# Mareltek_Glove_Project_esp32.net
KiCad netlist of a schematic drawn in EAGLE
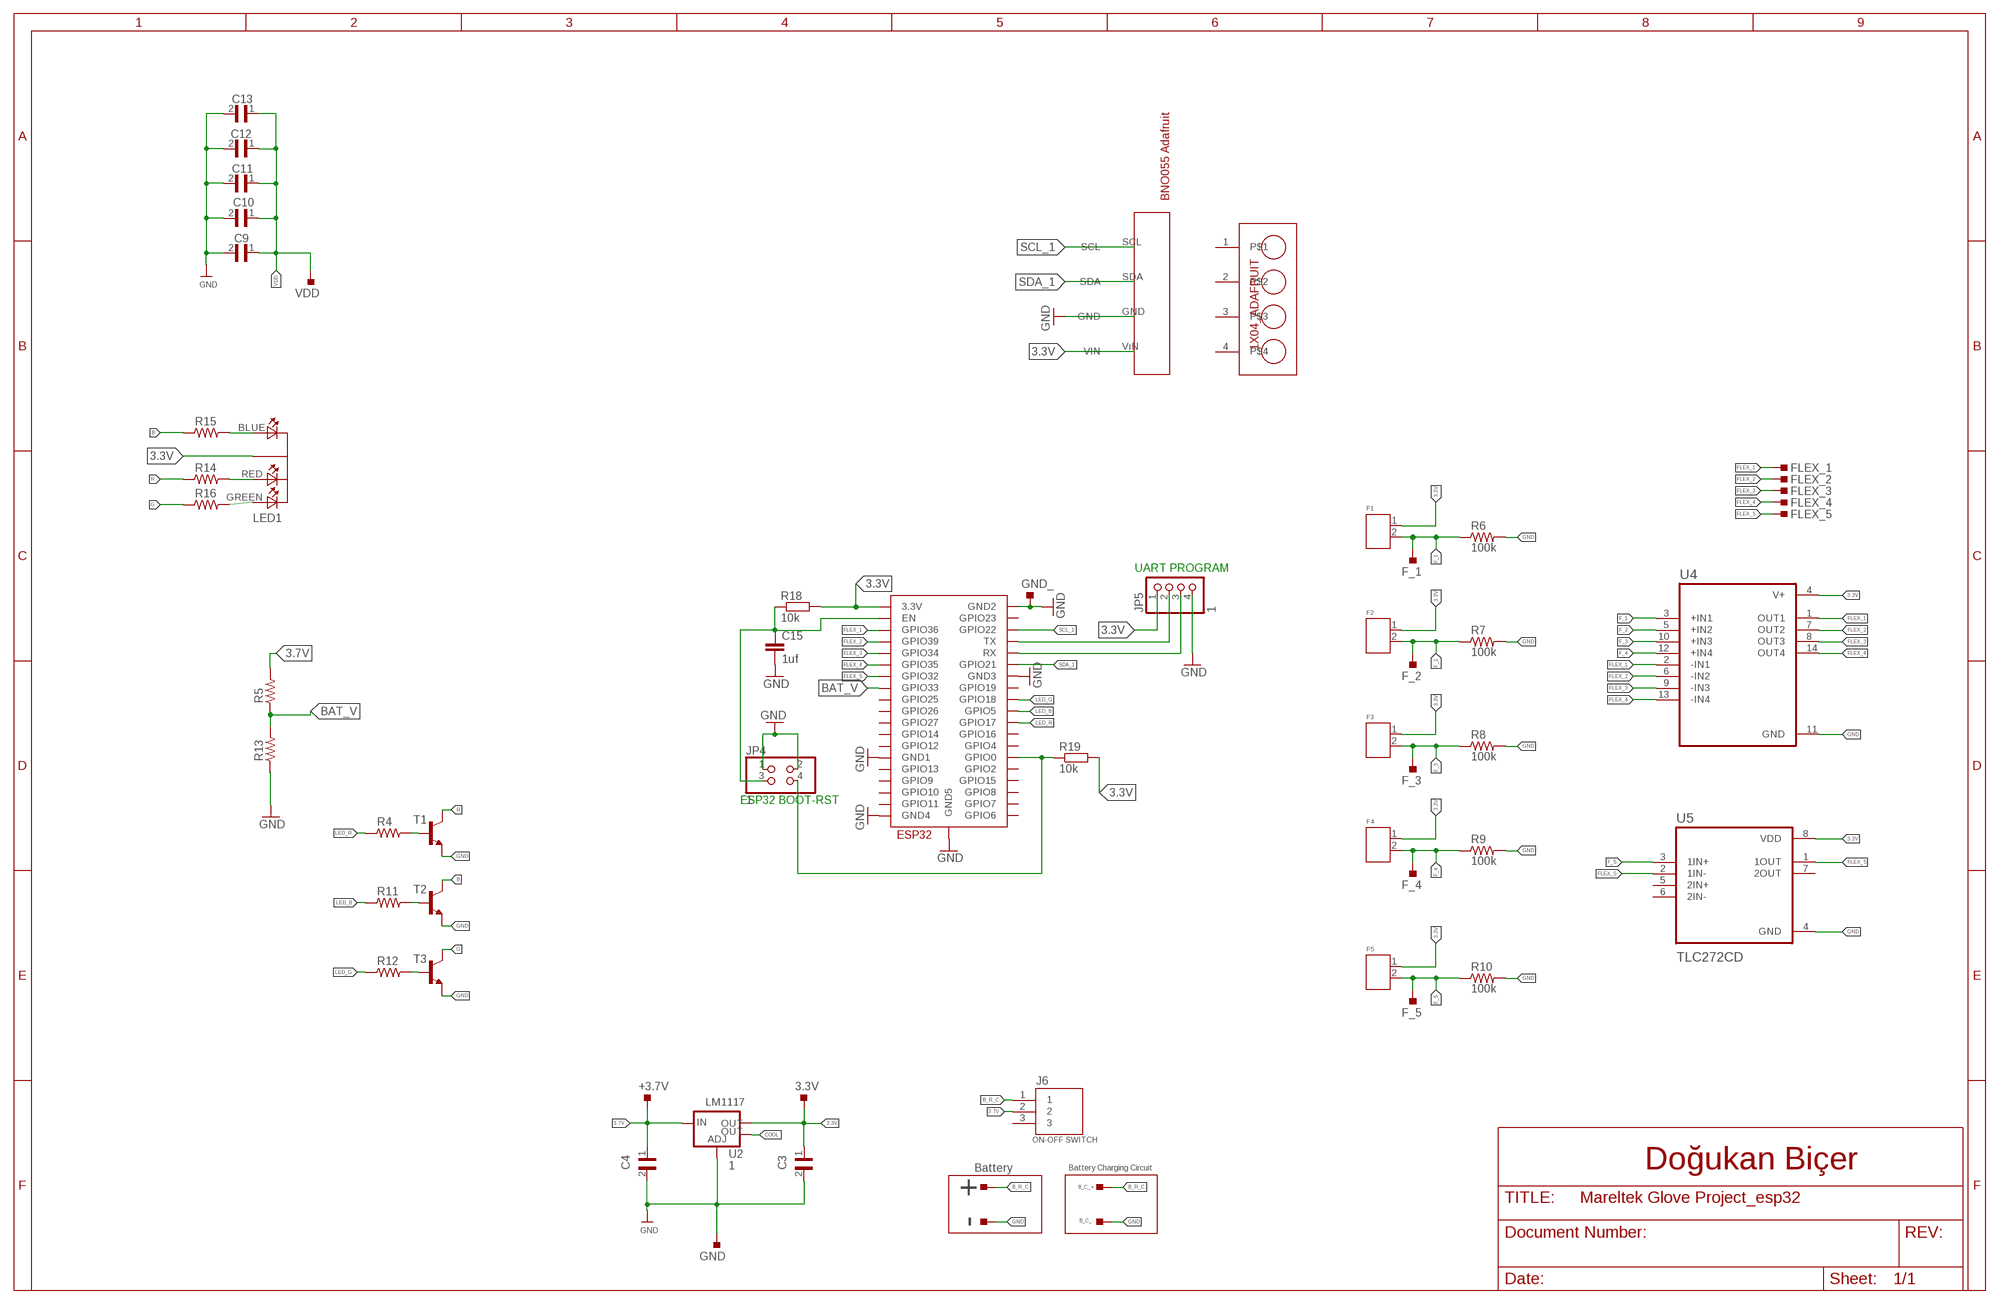
[diagram p0: schematic, sheet 1]

(export (version "E")
  (design (tool "Eeschema 10.0.6"))
  (components
    (comp (ref "+")
      (value "TESTPOINT_TPS-PAD-036")
      (footprint "eagle-import:TESTPOINT_PAD-036")
      (libsource (lib "eagle-import") (part "TESTPOINT_TPS-PAD-036"))
    )
    (comp (ref "+3.7V")
      (value "TESTPOINT_TPS-SMD-10SN")
      (footprint "eagle-import:TESTPOINT_SMD-10SN")
      (libsource (lib "eagle-import") (part "Mareltek Detector Hand Library_TESTPOINT_TPS-SMD-10SN"))
    )
    (comp (ref "-")
      (value "TESTPOINT_TPS-PAD-036")
      (footprint "eagle-import:TESTPOINT_PAD-036")
      (libsource (lib "eagle-import") (part "TESTPOINT_TPS-PAD-036"))
    )
    (comp (ref "3.3V")
      (value "TESTPOINT_TPS-SMD-10SN")
      (footprint "eagle-import:TESTPOINT_SMD-10SN")
      (libsource (lib "eagle-import") (part "Mareltek Detector Hand Library_TESTPOINT_TPS-SMD-10SN"))
    )
    (comp (ref "B_C_+")
      (value "TESTPOINT_TPS-PAD-036")
      (footprint "eagle-import:TESTPOINT_PAD-036")
      (libsource (lib "eagle-import") (part "TESTPOINT_TPS-PAD-036"))
    )
    (comp (ref "B_C_-")
      (value "TESTPOINT_TPS-PAD-036")
      (footprint "eagle-import:TESTPOINT_PAD-036")
      (libsource (lib "eagle-import") (part "TESTPOINT_TPS-PAD-036"))
    )
    (comp (ref "C3")
      (value "10uF")
      (footprint "eagle-import:CAPC1608X90")
      (fields (field (name "MF") "AVX") (field (name "MP") "06033C391KAT4A") (field (name "SPICEPREFIX") "C"))
      (libsource (lib "eagle-import") (part "CAP_0603"))
    )
    (comp (ref "C4")
      (value "10uF")
      (footprint "eagle-import:CAPC1608X90")
      (fields (field (name "MF") "AVX") (field (name "MP") "06033C391KAT4A") (field (name "SPICEPREFIX") "C"))
      (libsource (lib "eagle-import") (part "CAP_0603"))
    )
    (comp (ref "C9")
      (value "100nF")
      (footprint "eagle-import:CAPC1608X90")
      (fields (field (name "MF") "AVX") (field (name "MP") "06033C391KAT4A") (field (name "SPICEPREFIX") "C"))
      (libsource (lib "eagle-import") (part "CAP_0603"))
    )
    (comp (ref "C10")
      (value "100nF")
      (footprint "eagle-import:CAPC1608X90")
      (fields (field (name "MF") "AVX") (field (name "MP") "06033C391KAT4A") (field (name "SPICEPREFIX") "C"))
      (libsource (lib "eagle-import") (part "CAP_0603"))
    )
    (comp (ref "C11")
      (value "100nF")
      (footprint "eagle-import:CAPC1608X90")
      (fields (field (name "MF") "AVX") (field (name "MP") "06033C391KAT4A") (field (name "SPICEPREFIX") "C"))
      (libsource (lib "eagle-import") (part "CAP_0603"))
    )
    (comp (ref "C12")
      (value "100nF")
      (footprint "eagle-import:CAPC1608X90")
      (fields (field (name "MF") "AVX") (field (name "MP") "06033C391KAT4A") (field (name "SPICEPREFIX") "C"))
      (libsource (lib "eagle-import") (part "CAP_0603"))
    )
    (comp (ref "C13")
      (value "100nF")
      (footprint "eagle-import:CAPC1608X90")
      (fields (field (name "MF") "AVX") (field (name "MP") "06033C391KAT4A") (field (name "SPICEPREFIX") "C"))
      (libsource (lib "eagle-import") (part "CAP_0603"))
    )
    (comp (ref "C15")
      (value "1uf")
      (footprint "eagle-import:C0805")
      (libsource (lib "eagle-import") (part "C-EUC0805"))
    )
    (comp (ref "F1")
      (value "FLEX_CONNECTOR")
      (footprint "eagle-import:FLEX_CONNECTOR")
      (libsource (lib "eagle-import") (part "FLEX_CONNECTOR"))
    )
    (comp (ref "F2")
      (value "FLEX_CONNECTOR")
      (footprint "eagle-import:FLEX_CONNECTOR")
      (libsource (lib "eagle-import") (part "FLEX_CONNECTOR"))
    )
    (comp (ref "F3")
      (value "FLEX_CONNECTOR")
      (footprint "eagle-import:FLEX_CONNECTOR")
      (libsource (lib "eagle-import") (part "FLEX_CONNECTOR"))
    )
    (comp (ref "F4")
      (value "FLEX_CONNECTOR")
      (footprint "eagle-import:FLEX_CONNECTOR")
      (libsource (lib "eagle-import") (part "FLEX_CONNECTOR"))
    )
    (comp (ref "F5")
      (value "FLEX_CONNECTOR")
      (footprint "eagle-import:FLEX_CONNECTOR")
      (libsource (lib "eagle-import") (part "FLEX_CONNECTOR"))
    )
    (comp (ref "FLEX_1")
      (value "TESTPOINT_TPS-SMD-10SN")
      (footprint "eagle-import:TESTPOINT_SMD-10SN")
      (libsource (lib "eagle-import") (part "Mareltek Detector Hand Library_TESTPOINT_TPS-SMD-10SN"))
    )
    (comp (ref "FLEX_2")
      (value "TESTPOINT_TPS-SMD-10SN")
      (footprint "eagle-import:TESTPOINT_SMD-10SN")
      (libsource (lib "eagle-import") (part "Mareltek Detector Hand Library_TESTPOINT_TPS-SMD-10SN"))
    )
    (comp (ref "FLEX_3")
      (value "TESTPOINT_TPS-SMD-10SN")
      (footprint "eagle-import:TESTPOINT_SMD-10SN")
      (libsource (lib "eagle-import") (part "Mareltek Detector Hand Library_TESTPOINT_TPS-SMD-10SN"))
    )
    (comp (ref "FLEX_4")
      (value "TESTPOINT_TPS-SMD-10SN")
      (footprint "eagle-import:TESTPOINT_SMD-10SN")
      (libsource (lib "eagle-import") (part "Mareltek Detector Hand Library_TESTPOINT_TPS-SMD-10SN"))
    )
    (comp (ref "FLEX_5")
      (value "TESTPOINT_TPS-SMD-10SN")
      (footprint "eagle-import:TESTPOINT_SMD-10SN")
      (libsource (lib "eagle-import") (part "Mareltek Detector Hand Library_TESTPOINT_TPS-SMD-10SN"))
    )
    (comp (ref "F_1")
      (value "TESTPOINT_TPS-SMD-10SN")
      (footprint "eagle-import:TESTPOINT_SMD-10SN")
      (libsource (lib "eagle-import") (part "Mareltek Detector Hand Library_TESTPOINT_TPS-SMD-10SN"))
    )
    (comp (ref "F_2")
      (value "TESTPOINT_TPS-SMD-10SN")
      (footprint "eagle-import:TESTPOINT_SMD-10SN")
      (libsource (lib "eagle-import") (part "Mareltek Detector Hand Library_TESTPOINT_TPS-SMD-10SN"))
    )
    (comp (ref "F_3")
      (value "TESTPOINT_TPS-SMD-10SN")
      (footprint "eagle-import:TESTPOINT_SMD-10SN")
      (libsource (lib "eagle-import") (part "Mareltek Detector Hand Library_TESTPOINT_TPS-SMD-10SN"))
    )
    (comp (ref "F_4")
      (value "TESTPOINT_TPS-SMD-10SN")
      (footprint "eagle-import:TESTPOINT_SMD-10SN")
      (libsource (lib "eagle-import") (part "Mareltek Detector Hand Library_TESTPOINT_TPS-SMD-10SN"))
    )
    (comp (ref "F_5")
      (value "TESTPOINT_TPS-SMD-10SN")
      (footprint "eagle-import:TESTPOINT_SMD-10SN")
      (libsource (lib "eagle-import") (part "Mareltek Detector Hand Library_TESTPOINT_TPS-SMD-10SN"))
    )
    (comp (ref "GND")
      (value "TESTPOINT_TPS-SMD-10SN")
      (footprint "eagle-import:TESTPOINT_SMD-10SN")
      (libsource (lib "eagle-import") (part "Mareltek Detector Hand Library_TESTPOINT_TPS-SMD-10SN"))
    )
    (comp (ref "GND_")
      (value "TESTPOINT_TPS-SMD-10SN")
      (footprint "eagle-import:TESTPOINT_SMD-10SN")
      (libsource (lib "eagle-import") (part "Mareltek Detector Hand Library_TESTPOINT_TPS-SMD-10SN"))
    )
    (comp (ref "J6")
      (value "ON-OFF SWITCH")
      (footprint "eagle-import:TE_5-146293-3")
      (fields
        (field (name "COMMENT") "5-146293-3")
        (field (name "MF") "TE Connectivity")
        (field (name "SPICEPREFIX") "J")
      )
      (libsource (lib "eagle-import") (part "BUTTONS"))
    )
    (comp (ref "JP4")
      (value "1")
      (footprint "eagle-import:2X02")
      (libsource (lib "eagle-import") (part "PINHD-2X2"))
    )
    (comp (ref "JP5")
      (value "1")
      (footprint "eagle-import:1X04")
      (libsource (lib "eagle-import") (part "PINHD-1X4"))
    )
    (comp (ref "LED1")
      (value "LED-DIP-3")
      (footprint "eagle-import:DIP-4")
      (libsource (lib "eagle-import") (part "LED-DIP-3"))
    )
    (comp (ref "R4")
      (value "100R")
      (footprint "eagle-import:RC-MASTER-SMD_R0603MP")
      (fields (field (name "SPICEPREFIX") "R"))
      (libsource (lib "eagle-import") (part "RC-MASTER-SMD_RESISTOR0603MP"))
    )
    (comp (ref "R5")
      (value "100k")
      (footprint "eagle-import:RC-MASTER-SMD_R0603MP")
      (fields (field (name "SPICEPREFIX") "R"))
      (libsource (lib "eagle-import") (part "RC-MASTER-SMD_RESISTOR0603MP"))
    )
    (comp (ref "R6")
      (value "100k")
      (footprint "eagle-import:RC-MASTER-SMD_R0603MP")
      (fields (field (name "SPICEPREFIX") "W"))
      (libsource (lib "eagle-import") (part "RC-MASTER-SMD_RESISTOR0603MP"))
    )
    (comp (ref "R7")
      (value "100k")
      (footprint "eagle-import:RC-MASTER-SMD_R0603MP")
      (fields (field (name "SPICEPREFIX") "W"))
      (libsource (lib "eagle-import") (part "RC-MASTER-SMD_RESISTOR0603MP"))
    )
    (comp (ref "R8")
      (value "100k")
      (footprint "eagle-import:RC-MASTER-SMD_R0603MP")
      (fields (field (name "SPICEPREFIX") "W"))
      (libsource (lib "eagle-import") (part "RC-MASTER-SMD_RESISTOR0603MP"))
    )
    (comp (ref "R9")
      (value "100k")
      (footprint "eagle-import:RC-MASTER-SMD_R0603MP")
      (fields (field (name "SPICEPREFIX") "W"))
      (libsource (lib "eagle-import") (part "RC-MASTER-SMD_RESISTOR0603MP"))
    )
    (comp (ref "R10")
      (value "100k")
      (footprint "eagle-import:RC-MASTER-SMD_R0603MP")
      (fields (field (name "SPICEPREFIX") "W"))
      (libsource (lib "eagle-import") (part "RC-MASTER-SMD_RESISTOR0603MP"))
    )
    (comp (ref "R11")
      (value "100R")
      (footprint "eagle-import:RC-MASTER-SMD_R0603MP")
      (fields (field (name "SPICEPREFIX") "R"))
      (libsource (lib "eagle-import") (part "RC-MASTER-SMD_RESISTOR0603MP"))
    )
    (comp (ref "R12")
      (value "100R")
      (footprint "eagle-import:RC-MASTER-SMD_R0603MP")
      (fields (field (name "SPICEPREFIX") "R"))
      (libsource (lib "eagle-import") (part "RC-MASTER-SMD_RESISTOR0603MP"))
    )
    (comp (ref "R13")
      (value "330R")
      (footprint "eagle-import:RC-MASTER-SMD_R0603MP")
      (fields (field (name "SPICEPREFIX") "R"))
      (libsource (lib "eagle-import") (part "RC-MASTER-SMD_RESISTOR0603MP"))
    )
    (comp (ref "R14")
      (value "100R")
      (footprint "eagle-import:RC-MASTER-SMD_R0603MP")
      (fields (field (name "SPICEPREFIX") "R"))
      (libsource (lib "eagle-import") (part "RC-MASTER-SMD_RESISTOR0603MP"))
    )
    (comp (ref "R15")
      (value "100R")
      (footprint "eagle-import:RC-MASTER-SMD_R0603MP")
      (fields (field (name "SPICEPREFIX") "R"))
      (libsource (lib "eagle-import") (part "RC-MASTER-SMD_RESISTOR0603MP"))
    )
    (comp (ref "R16")
      (value "100R")
      (footprint "eagle-import:RC-MASTER-SMD_R0603MP")
      (fields (field (name "SPICEPREFIX") "R"))
      (libsource (lib "eagle-import") (part "RC-MASTER-SMD_RESISTOR0603MP"))
    )
    (comp (ref "R18")
      (value "10k")
      (footprint "eagle-import:R0603")
      (libsource (lib "eagle-import") (part "R-EU_R0603"))
    )
    (comp (ref "R19")
      (value "10k")
      (footprint "eagle-import:R0603")
      (libsource (lib "eagle-import") (part "R-EU_R0603"))
    )
    (comp (ref "T1")
      (value "TRANSISTORBC846BLT1SOT23-BEC")
      (footprint "eagle-import:SOT23-BEC")
      (libsource (lib "eagle-import") (part "TRANSISTORSOT23-BECBC846BLT1"))
    )
    (comp (ref "T2")
      (value "TRANSISTORBC846BLT1SOT23-BEC")
      (footprint "eagle-import:SOT23-BEC")
      (libsource (lib "eagle-import") (part "TRANSISTORSOT23-BECBC846BLT1"))
    )
    (comp (ref "T3")
      (value "TRANSISTORBC846BLT1SOT23-BEC")
      (footprint "eagle-import:SOT23-BEC")
      (libsource (lib "eagle-import") (part "TRANSISTORSOT23-BECBC846BLT1"))
    )
    (comp (ref "U$2")
      (value "BNO055_ADAFRUIT")
      (footprint "eagle-import:1X06_ROUND_76")
      (libsource (lib "eagle-import") (part "BNO055_ADAFRUIT"))
    )
    (comp (ref "U$4")
      (value "1X04_ADAFRUIT")
      (footprint "eagle-import:1X04_ROUND_76")
      (libsource (lib "eagle-import") (part "1X04_ADAFRUIT"))
    )
    (comp (ref "U$7")
      (value "ESP32-WROOM")
      (footprint "eagle-import:ESP32-WROOM")
      (libsource (lib "eagle-import") (part "ESP32-WROOM"))
    )
    (comp (ref "U2")
      (value "1")
      (footprint "eagle-import:SOT223")
      (libsource (lib "eagle-import") (part "LM1117_V_REGULATORSOT223"))
    )
    (comp (ref "U4")
      (value "LM324")
      (footprint "eagle-import:SOIC127P600X175-14N")
      (fields
        (field (name "MF") "Texas Instruments")
        (field (name "MP") "LM324M")
        (field (name "SPICEPREFIX") "X")
      )
      (libsource (lib "eagle-import") (part "LM324M"))
    )
    (comp (ref "U5")
      (value "TLC272CD")
      (footprint "eagle-import:SOIC127P599X175-8N")
      (fields (field (name "MF") "Texas Instruments"))
      (libsource (lib "eagle-import") (part "TLC272CD"))
    )
    (comp (ref "VDD")
      (value "TESTPOINT_TPS-SMD-10SN")
      (footprint "eagle-import:TESTPOINT_SMD-10SN")
      (libsource (lib "eagle-import") (part "Mareltek Detector Hand Library_TESTPOINT_TPS-SMD-10SN"))
    )
  )
  (nets
    (net (code "1") (name "3.3V") (class "Default")
      (node (ref "3.3V") (pin "TP") (pinfunction "TP_TP") (pintype "passive"))
      (node (ref "C3") (pin "1") (pinfunction "1_1") (pintype "passive"))
      (node (ref "F1") (pin "1") (pinfunction "P$1_1") (pintype "bidirectional"))
      (node (ref "F2") (pin "1") (pinfunction "P$1_1") (pintype "bidirectional"))
      (node (ref "F3") (pin "1") (pinfunction "P$1_1") (pintype "bidirectional"))
      (node (ref "F4") (pin "1") (pinfunction "P$1_1") (pintype "bidirectional"))
      (node (ref "F5") (pin "1") (pinfunction "P$1_1") (pintype "bidirectional"))
      (node (ref "JP5") (pin "1") (pinfunction "1_1") (pintype "passive"))
      (node (ref "LED1") (pin "COMMON_CATHODE") (pinfunction "COM-CATHODE_COMMON_CATHODE") (pintype "passive"))
      (node (ref "R18") (pin "2") (pinfunction "2_2") (pintype "passive"))
      (node (ref "R19") (pin "2") (pinfunction "2_2") (pintype "passive"))
      (node (ref "U$2") (pin "VıN") (pinfunction "VIN_VıN") (pintype "bidirectional"))
      (node (ref "U$7") (pin "3V3") (pinfunction "3.3V_3V3") (pintype "bidirectional"))
      (node (ref "U2") (pin "2") (pinfunction "OUT_2") (pintype "output"))
      (node (ref "U4") (pin "4") (pinfunction "V+_4") (pintype "power_in"))
      (node (ref "U5") (pin "8") (pinfunction "VDD_8") (pintype "power_in"))
    )
    (net (code "2") (name "3.7V") (class "Default")
      (node (ref "+3.7V") (pin "TP") (pinfunction "TP_TP") (pintype "passive"))
      (node (ref "C4") (pin "1") (pinfunction "1_1") (pintype "passive"))
      (node (ref "J6") (pin "2") (pinfunction "2_2") (pintype "passive"))
      (node (ref "R5") (pin "2") (pinfunction "2_2") (pintype "passive"))
      (node (ref "U2") (pin "3") (pinfunction "IN_3") (pintype "input"))
    )
    (net (code "3") (name "B") (class "Default")
      (node (ref "R15") (pin "1") (pinfunction "1_1") (pintype "passive"))
      (node (ref "T2") (pin "C") (pinfunction "C_C") (pintype "passive"))
    )
    (net (code "4") (name "BAT_V") (class "Default")
      (node (ref "R13") (pin "2") (pinfunction "2_2") (pintype "passive"))
      (node (ref "R5") (pin "1") (pinfunction "1_1") (pintype "passive"))
      (node (ref "U$7") (pin "IO33") (pinfunction "GPIO33_IO33") (pintype "bidirectional"))
    )
    (net (code "5") (name "B_R_C") (class "Default")
      (node (ref "+") (pin "1") (pinfunction "TP_1") (pintype "passive"))
      (node (ref "B_C_+") (pin "1") (pinfunction "TP_1") (pintype "passive"))
      (node (ref "J6") (pin "1") (pinfunction "1_1") (pintype "passive"))
    )
    (net (code "6") (name "COOL") (class "Default")
      (node (ref "U2") (pin "4") (pinfunction "OUT_4") (pintype "output"))
    )
    (net (code "7") (name "FLEX_1") (class "Default")
      (node (ref "FLEX_1") (pin "TP") (pinfunction "TP_TP") (pintype "passive"))
      (node (ref "U$7") (pin "SENSOR_VP") (pinfunction "GPIO36_SENSOR_VP") (pintype "bidirectional"))
      (node (ref "U4") (pin "1") (pinfunction "OUT1_1") (pintype "output"))
      (node (ref "U4") (pin "2") (pinfunction "-IN1_2") (pintype "input"))
    )
    (net (code "8") (name "FLEX_2") (class "Default")
      (node (ref "FLEX_2") (pin "TP") (pinfunction "TP_TP") (pintype "passive"))
      (node (ref "U$7") (pin "SENSOR_VN") (pinfunction "GPIO39_SENSOR_VN") (pintype "bidirectional"))
      (node (ref "U4") (pin "6") (pinfunction "-IN2_6") (pintype "input"))
      (node (ref "U4") (pin "7") (pinfunction "OUT2_7") (pintype "output"))
    )
    (net (code "9") (name "FLEX_3") (class "Default")
      (node (ref "FLEX_3") (pin "TP") (pinfunction "TP_TP") (pintype "passive"))
      (node (ref "U$7") (pin "IO34") (pinfunction "GPIO34_IO34") (pintype "bidirectional"))
      (node (ref "U4") (pin "8") (pinfunction "OUT3_8") (pintype "output"))
      (node (ref "U4") (pin "9") (pinfunction "-IN3_9") (pintype "input"))
    )
    (net (code "10") (name "FLEX_4") (class "Default")
      (node (ref "FLEX_4") (pin "TP") (pinfunction "TP_TP") (pintype "passive"))
      (node (ref "U$7") (pin "IO35") (pinfunction "GPIO35_IO35") (pintype "bidirectional"))
      (node (ref "U4") (pin "13") (pinfunction "-IN4_13") (pintype "input"))
      (node (ref "U4") (pin "14") (pinfunction "OUT4_14") (pintype "output"))
    )
    (net (code "11") (name "FLEX_5") (class "Default")
      (node (ref "FLEX_5") (pin "TP") (pinfunction "TP_TP") (pintype "passive"))
      (node (ref "U$7") (pin "IO32") (pinfunction "GPIO32_IO32") (pintype "bidirectional"))
      (node (ref "U5") (pin "1") (pinfunction "1OUT_1") (pintype "output"))
      (node (ref "U5") (pin "2") (pinfunction "1IN-_2") (pintype "input"))
    )
    (net (code "12") (name "F_1") (class "Default")
      (node (ref "F1") (pin "2") (pinfunction "P$2_2") (pintype "bidirectional"))
      (node (ref "F_1") (pin "TP") (pinfunction "TP_TP") (pintype "passive"))
      (node (ref "R6") (pin "1") (pinfunction "1_1") (pintype "passive"))
      (node (ref "U4") (pin "3") (pinfunction "+IN1_3") (pintype "input"))
    )
    (net (code "13") (name "F_2") (class "Default")
      (node (ref "F2") (pin "2") (pinfunction "P$2_2") (pintype "bidirectional"))
      (node (ref "F_2") (pin "TP") (pinfunction "TP_TP") (pintype "passive"))
      (node (ref "R7") (pin "1") (pinfunction "1_1") (pintype "passive"))
      (node (ref "U4") (pin "5") (pinfunction "+IN2_5") (pintype "input"))
    )
    (net (code "14") (name "F_3") (class "Default")
      (node (ref "F3") (pin "2") (pinfunction "P$2_2") (pintype "bidirectional"))
      (node (ref "F_3") (pin "TP") (pinfunction "TP_TP") (pintype "passive"))
      (node (ref "R8") (pin "1") (pinfunction "1_1") (pintype "passive"))
      (node (ref "U4") (pin "10") (pinfunction "+IN3_10") (pintype "input"))
    )
    (net (code "15") (name "F_4") (class "Default")
      (node (ref "F4") (pin "2") (pinfunction "P$2_2") (pintype "bidirectional"))
      (node (ref "F_4") (pin "TP") (pinfunction "TP_TP") (pintype "passive"))
      (node (ref "R9") (pin "1") (pinfunction "1_1") (pintype "passive"))
      (node (ref "U4") (pin "12") (pinfunction "+IN4_12") (pintype "input"))
    )
    (net (code "16") (name "F_5") (class "Default")
      (node (ref "F5") (pin "2") (pinfunction "P$2_2") (pintype "bidirectional"))
      (node (ref "F_5") (pin "TP") (pinfunction "TP_TP") (pintype "passive"))
      (node (ref "R10") (pin "1") (pinfunction "1_1") (pintype "passive"))
      (node (ref "U5") (pin "3") (pinfunction "1IN+_3") (pintype "input"))
    )
    (net (code "17") (name "G") (class "Default")
      (node (ref "R16") (pin "1") (pinfunction "1_1") (pintype "passive"))
      (node (ref "T3") (pin "C") (pinfunction "C_C") (pintype "passive"))
    )
    (net (code "18") (name "GND") (class "Default")
      (node (ref "-") (pin "1") (pinfunction "TP_1") (pintype "passive"))
      (node (ref "B_C_-") (pin "1") (pinfunction "TP_1") (pintype "passive"))
      (node (ref "C10") (pin "2") (pinfunction "2_2") (pintype "passive"))
      (node (ref "C11") (pin "2") (pinfunction "2_2") (pintype "passive"))
      (node (ref "C12") (pin "2") (pinfunction "2_2") (pintype "passive"))
      (node (ref "C13") (pin "2") (pinfunction "2_2") (pintype "passive"))
      (node (ref "C15") (pin "2") (pinfunction "2_2") (pintype "passive"))
      (node (ref "C3") (pin "2") (pinfunction "2_2") (pintype "passive"))
      (node (ref "C4") (pin "2") (pinfunction "2_2") (pintype "passive"))
      (node (ref "C9") (pin "2") (pinfunction "2_2") (pintype "passive"))
      (node (ref "GND") (pin "TP") (pinfunction "TP_TP") (pintype "passive"))
      (node (ref "GND_") (pin "TP") (pinfunction "TP_TP") (pintype "passive"))
      (node (ref "JP4") (pin "1") (pinfunction "1_1") (pintype "passive"))
      (node (ref "JP4") (pin "2") (pinfunction "2_2") (pintype "passive"))
      (node (ref "JP5") (pin "4") (pinfunction "4_4") (pintype "passive"))
      (node (ref "R10") (pin "2") (pinfunction "2_2") (pintype "passive"))
      (node (ref "R13") (pin "1") (pinfunction "1_1") (pintype "passive"))
      (node (ref "R6") (pin "2") (pinfunction "2_2") (pintype "passive"))
      (node (ref "R7") (pin "2") (pinfunction "2_2") (pintype "passive"))
      (node (ref "R8") (pin "2") (pinfunction "2_2") (pintype "passive"))
      (node (ref "R9") (pin "2") (pinfunction "2_2") (pintype "passive"))
      (node (ref "T1") (pin "E") (pinfunction "E_E") (pintype "passive"))
      (node (ref "T2") (pin "E") (pinfunction "E_E") (pintype "passive"))
      (node (ref "T3") (pin "E") (pinfunction "E_E") (pintype "passive"))
      (node (ref "U$2") (pin "GND") (pinfunction "GND_GND") (pintype "bidirectional"))
      (node (ref "U$7") (pin "GND1") (pinfunction "GND1_GND1") (pintype "bidirectional"))
      (node (ref "U$7") (pin "GND2") (pinfunction "GND2_GND2") (pintype "bidirectional"))
      (node (ref "U$7") (pin "GND3") (pinfunction "GND3_GND3") (pintype "bidirectional"))
      (node (ref "U$7") (pin "GND4") (pinfunction "GND4_GND4") (pintype "bidirectional"))
      (node (ref "U$7") (pin "GND5") (pinfunction "GND5_GND5") (pintype "bidirectional"))
      (node (ref "U2") (pin "1") (pinfunction "ADJ_1") (pintype "input"))
      (node (ref "U4") (pin "11") (pinfunction "GND_11") (pintype "power_in"))
      (node (ref "U5") (pin "4") (pinfunction "GND_4") (pintype "power_in"))
    )
    (net (code "19") (name "LED_B") (class "Default")
      (node (ref "R11") (pin "1") (pinfunction "1_1") (pintype "passive"))
      (node (ref "U$7") (pin "IO5") (pinfunction "GPIO5_IO5") (pintype "bidirectional"))
    )
    (net (code "20") (name "LED_G") (class "Default")
      (node (ref "R12") (pin "1") (pinfunction "1_1") (pintype "passive"))
      (node (ref "U$7") (pin "IO18") (pinfunction "GPIO18_IO18") (pintype "bidirectional"))
    )
    (net (code "21") (name "LED_R") (class "Default")
      (node (ref "R4") (pin "1") (pinfunction "1_1") (pintype "passive"))
      (node (ref "U$7") (pin "IO17") (pinfunction "GPIO17_IO17") (pintype "bidirectional"))
    )
    (net (code "22") (name "Net-(C15-Pad1)") (class "Default")
      (node (ref "C15") (pin "1") (pinfunction "1_1") (pintype "passive"))
      (node (ref "JP4") (pin "3") (pinfunction "3_3") (pintype "passive"))
      (node (ref "R18") (pin "1") (pinfunction "1_1") (pintype "passive"))
      (node (ref "U$7") (pin "EN") (pinfunction "EN_EN") (pintype "bidirectional"))
    )
    (net (code "23") (name "Net-(JP5-Pad2)") (class "Default")
      (node (ref "JP5") (pin "2") (pinfunction "2_2") (pintype "passive"))
      (node (ref "U$7") (pin "TX") (pinfunction "TX_TX") (pintype "bidirectional"))
    )
    (net (code "24") (name "Net-(JP5-Pad3)") (class "Default")
      (node (ref "JP5") (pin "3") (pinfunction "3_3") (pintype "passive"))
      (node (ref "U$7") (pin "RX") (pinfunction "RX_RX") (pintype "bidirectional"))
    )
    (net (code "25") (name "Net-(LED1-PadBLUE)") (class "Default")
      (node (ref "LED1") (pin "BLUE") (pinfunction "BLUE_BLUE") (pintype "passive"))
      (node (ref "R15") (pin "2") (pinfunction "2_2") (pintype "passive"))
    )
    (net (code "26") (name "Net-(LED1-PadGREEN)") (class "Default")
      (node (ref "LED1") (pin "GREEN") (pinfunction "GREEN_GREEN") (pintype "passive"))
      (node (ref "R16") (pin "2") (pinfunction "2_2") (pintype "passive"))
    )
    (net (code "27") (name "Net-(LED1-PadRED)") (class "Default")
      (node (ref "LED1") (pin "RED") (pinfunction "RED_RED") (pintype "passive"))
      (node (ref "R14") (pin "2") (pinfunction "2_2") (pintype "passive"))
    )
    (net (code "28") (name "Net-(R4-Pad2)") (class "Default")
      (node (ref "R4") (pin "2") (pinfunction "2_2") (pintype "passive"))
      (node (ref "T1") (pin "B") (pinfunction "B_B") (pintype "passive"))
    )
    (net (code "29") (name "Net-(R11-Pad2)") (class "Default")
      (node (ref "R11") (pin "2") (pinfunction "2_2") (pintype "passive"))
      (node (ref "T2") (pin "B") (pinfunction "B_B") (pintype "passive"))
    )
    (net (code "30") (name "Net-(R12-Pad2)") (class "Default")
      (node (ref "R12") (pin "2") (pinfunction "2_2") (pintype "passive"))
      (node (ref "T3") (pin "B") (pinfunction "B_B") (pintype "passive"))
    )
    (net (code "31") (name "Net-(U$7-GPIO0)") (class "Default")
      (node (ref "JP4") (pin "4") (pinfunction "4_4") (pintype "passive"))
      (node (ref "R19") (pin "1") (pinfunction "1_1") (pintype "passive"))
      (node (ref "U$7") (pin "IO0") (pinfunction "GPIO0_IO0") (pintype "bidirectional"))
    )
    (net (code "32") (name "R") (class "Default")
      (node (ref "R14") (pin "1") (pinfunction "1_1") (pintype "passive"))
      (node (ref "T1") (pin "C") (pinfunction "C_C") (pintype "passive"))
    )
    (net (code "33") (name "SCL_1") (class "Default")
      (node (ref "U$2") (pin "SCL") (pinfunction "SCL_SCL") (pintype "bidirectional"))
      (node (ref "U$7") (pin "IO22") (pinfunction "GPIO22_IO22") (pintype "bidirectional"))
    )
    (net (code "34") (name "SDA_1") (class "Default")
      (node (ref "U$2") (pin "SDA") (pinfunction "SDA_SDA") (pintype "bidirectional"))
      (node (ref "U$7") (pin "IO21") (pinfunction "GPIO21_IO21") (pintype "bidirectional"))
    )
    (net (code "35") (name "VDD") (class "Default")
      (node (ref "C10") (pin "1") (pinfunction "1_1") (pintype "passive"))
      (node (ref "C11") (pin "1") (pinfunction "1_1") (pintype "passive"))
      (node (ref "C12") (pin "1") (pinfunction "1_1") (pintype "passive"))
      (node (ref "C13") (pin "1") (pinfunction "1_1") (pintype "passive"))
      (node (ref "C9") (pin "1") (pinfunction "1_1") (pintype "passive"))
      (node (ref "VDD") (pin "TP") (pinfunction "TP_TP") (pintype "passive"))
    )
    (net (code "36") (name "unconnected-(J6-Pad3)") (class "Default")
      (node (ref "J6") (pin "3") (pinfunction "3_3") (pintype "passive"))
    )
    (net (code "37") (name "unconnected-(U$4-P$1-Pad1)") (class "Default")
      (node (ref "U$4") (pin "1") (pinfunction "P$1_1") (pintype "bidirectional"))
    )
    (net (code "38") (name "unconnected-(U$4-P$2-Pad2)") (class "Default")
      (node (ref "U$4") (pin "2") (pinfunction "P$2_2") (pintype "bidirectional"))
    )
    (net (code "39") (name "unconnected-(U$4-P$3-Pad3)") (class "Default")
      (node (ref "U$4") (pin "3") (pinfunction "P$3_3") (pintype "bidirectional"))
    )
    (net (code "40") (name "unconnected-(U$4-P$4-Pad4)") (class "Default")
      (node (ref "U$4") (pin "4") (pinfunction "P$4_4") (pintype "bidirectional"))
    )
    (net (code "41") (name "unconnected-(U$7-GPIO2-PadIO2)") (class "Default")
      (node (ref "U$7") (pin "IO2") (pinfunction "GPIO2_IO2") (pintype "bidirectional"))
    )
    (net (code "42") (name "unconnected-(U$7-GPIO4-PadIO4)") (class "Default")
      (node (ref "U$7") (pin "IO4") (pinfunction "GPIO4_IO4") (pintype "bidirectional"))
    )
    (net (code "43") (name "unconnected-(U$7-GPIO6-PadCLK)") (class "Default")
      (node (ref "U$7") (pin "CLK") (pinfunction "GPIO6_CLK") (pintype "bidirectional"))
    )
    (net (code "44") (name "unconnected-(U$7-GPIO7-PadSD0)") (class "Default")
      (node (ref "U$7") (pin "SD0") (pinfunction "GPIO7_SD0") (pintype "bidirectional"))
    )
    (net (code "45") (name "unconnected-(U$7-GPIO8-PadSD1)") (class "Default")
      (node (ref "U$7") (pin "SD1") (pinfunction "GPIO8_SD1") (pintype "bidirectional"))
    )
    (net (code "46") (name "unconnected-(U$7-GPIO9-PadSD2)") (class "Default")
      (node (ref "U$7") (pin "SD2") (pinfunction "GPIO9_SD2") (pintype "bidirectional"))
    )
    (net (code "47") (name "unconnected-(U$7-GPIO10-PadSD3)") (class "Default")
      (node (ref "U$7") (pin "SD3") (pinfunction "GPIO10_SD3") (pintype "bidirectional"))
    )
    (net (code "48") (name "unconnected-(U$7-GPIO11-PadCMD)") (class "Default")
      (node (ref "U$7") (pin "CMD") (pinfunction "GPIO11_CMD") (pintype "bidirectional"))
    )
    (net (code "49") (name "unconnected-(U$7-GPIO12-PadIO12)") (class "Default")
      (node (ref "U$7") (pin "IO12") (pinfunction "GPIO12_IO12") (pintype "bidirectional"))
    )
    (net (code "50") (name "unconnected-(U$7-GPIO13-PadIO13)") (class "Default")
      (node (ref "U$7") (pin "IO13") (pinfunction "GPIO13_IO13") (pintype "bidirectional"))
    )
    (net (code "51") (name "unconnected-(U$7-GPIO14-PadIO14)") (class "Default")
      (node (ref "U$7") (pin "IO14") (pinfunction "GPIO14_IO14") (pintype "bidirectional"))
    )
    (net (code "52") (name "unconnected-(U$7-GPIO15-PadIO15)") (class "Default")
      (node (ref "U$7") (pin "IO15") (pinfunction "GPIO15_IO15") (pintype "bidirectional"))
    )
    (net (code "53") (name "unconnected-(U$7-GPIO16-PadIO16)") (class "Default")
      (node (ref "U$7") (pin "IO16") (pinfunction "GPIO16_IO16") (pintype "bidirectional"))
    )
    (net (code "54") (name "unconnected-(U$7-GPIO19-PadIO19)") (class "Default")
      (node (ref "U$7") (pin "IO19") (pinfunction "GPIO19_IO19") (pintype "bidirectional"))
    )
    (net (code "55") (name "unconnected-(U$7-GPIO23-PadIO23)") (class "Default")
      (node (ref "U$7") (pin "IO23") (pinfunction "GPIO23_IO23") (pintype "bidirectional"))
    )
    (net (code "56") (name "unconnected-(U$7-GPIO25-PadIO25)") (class "Default")
      (node (ref "U$7") (pin "IO25") (pinfunction "GPIO25_IO25") (pintype "bidirectional"))
    )
    (net (code "57") (name "unconnected-(U$7-GPIO26-PadIO26)") (class "Default")
      (node (ref "U$7") (pin "IO26") (pinfunction "GPIO26_IO26") (pintype "bidirectional"))
    )
    (net (code "58") (name "unconnected-(U$7-GPIO27-PadIO27)") (class "Default")
      (node (ref "U$7") (pin "IO27") (pinfunction "GPIO27_IO27") (pintype "bidirectional"))
    )
    (net (code "59") (name "unconnected-(U5-2IN+-Pad5)") (class "Default")
      (node (ref "U5") (pin "5") (pinfunction "2IN+_5") (pintype "input"))
    )
    (net (code "60") (name "unconnected-(U5-2IN--Pad6)") (class "Default")
      (node (ref "U5") (pin "6") (pinfunction "2IN-_6") (pintype "input"))
    )
    (net (code "61") (name "unconnected-(U5-2OUT-Pad7)") (class "Default")
      (node (ref "U5") (pin "7") (pinfunction "2OUT_7") (pintype "output"))
    )
  )
)
